# RFFE.net
KiCad netlist of a schematic drawn in Altium Designer
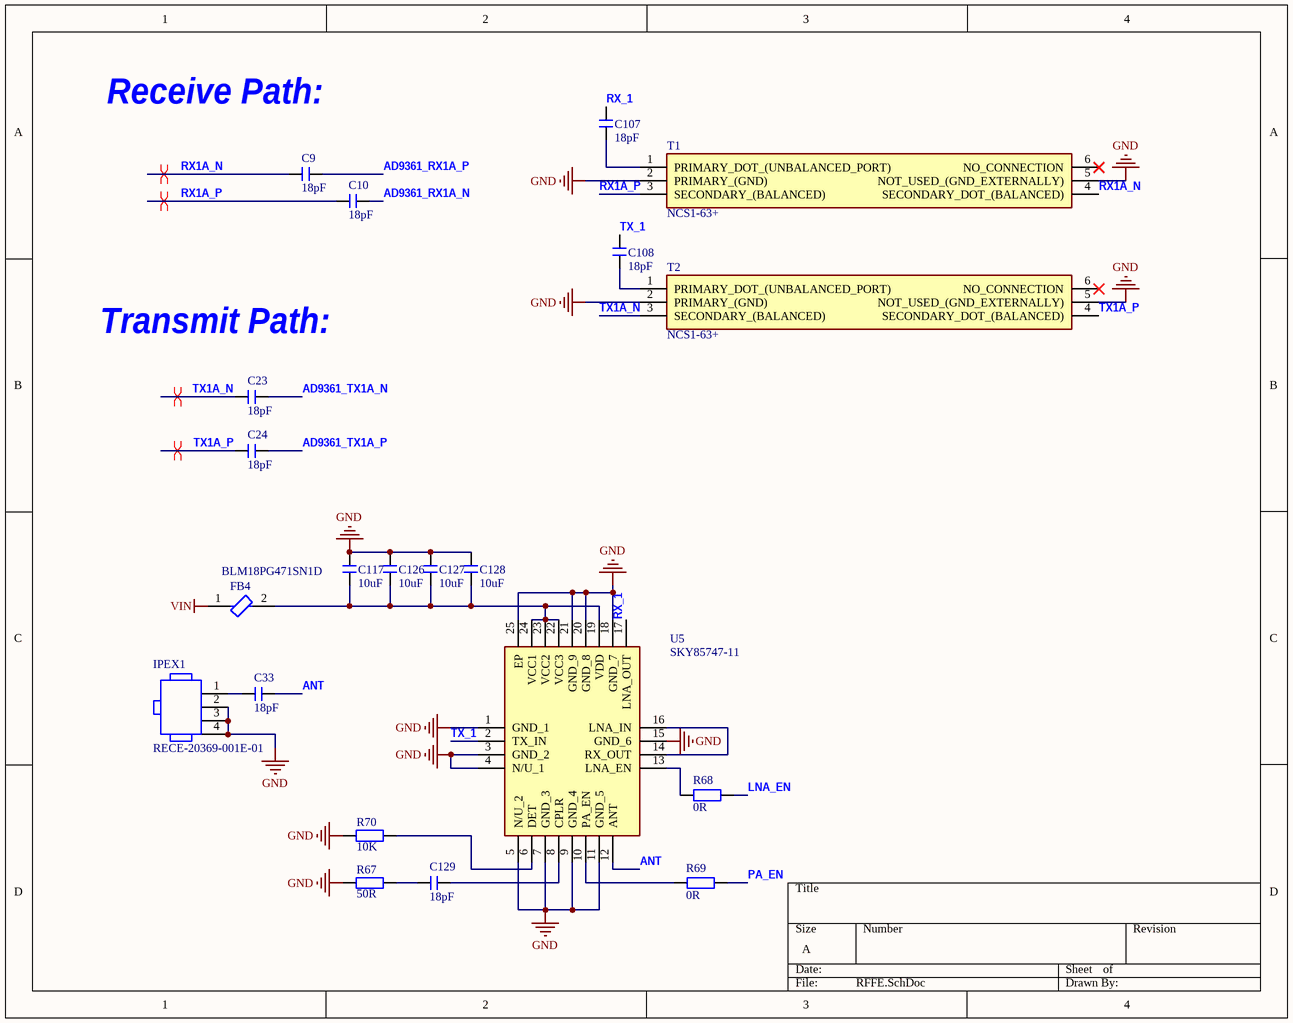
[diagram p0: RFFE.SchDoc]

(export (version "E")
  (design (tool "Eeschema 10.0.6"))
  (components
    (comp (ref "C9")
      (value "18pF")
      (footprint "SamacSys:CAP_0201")
      (description "无极性贴片电容")
      (fields (field (name "版权归属") "源创客"))
      (libsource (lib "源创客") (part "C"))
    )
    (comp (ref "C10")
      (value "18pF")
      (footprint "SamacSys:CAP_0201")
      (description "无极性贴片电容")
      (fields (field (name "版权归属") "源创客"))
      (libsource (lib "源创客") (part "C"))
    )
    (comp (ref "C23")
      (value "18pF")
      (footprint "SamacSys:CAP_0201")
      (description "无极性贴片电容")
      (fields (field (name "版权归属") "源创客"))
      (libsource (lib "源创客") (part "C"))
    )
    (comp (ref "C24")
      (value "18pF")
      (footprint "SamacSys:CAP_0201")
      (description "无极性贴片电容")
      (fields (field (name "版权归属") "源创客"))
      (libsource (lib "源创客") (part "C"))
    )
    (comp (ref "C33")
      (value "18pF")
      (footprint "SamacSys:CAP_0201")
      (description "无极性贴片电容")
      (fields (field (name "版权归属") "源创客"))
      (libsource (lib "源创客") (part "C"))
    )
    (comp (ref "C107")
      (value "18pF")
      (footprint "SamacSys:CAP_0201")
      (description "无极性贴片电容")
      (fields (field (name "版权归属") "源创客"))
      (libsource (lib "源创客") (part "C"))
    )
    (comp (ref "C108")
      (value "18pF")
      (footprint "SamacSys:CAP_0201")
      (description "无极性贴片电容")
      (fields (field (name "版权归属") "源创客"))
      (libsource (lib "源创客") (part "C"))
    )
    (comp (ref "C117")
      (value "10uF")
      (footprint "SamacSys:CAP_0402")
      (description "无极性贴片电容")
      (fields (field (name "版权归属") "源创客"))
      (libsource (lib "源创客") (part "C"))
    )
    (comp (ref "C126")
      (value "10uF")
      (footprint "SamacSys:CAP_0402")
      (description "无极性贴片电容")
      (fields (field (name "版权归属") "源创客"))
      (libsource (lib "源创客") (part "C"))
    )
    (comp (ref "C127")
      (value "10uF")
      (footprint "SamacSys:CAP_0402")
      (description "无极性贴片电容")
      (fields (field (name "版权归属") "源创客"))
      (libsource (lib "源创客") (part "C"))
    )
    (comp (ref "C128")
      (value "10uF")
      (footprint "SamacSys:CAP_0402")
      (description "无极性贴片电容")
      (fields (field (name "版权归属") "源创客"))
      (libsource (lib "源创客") (part "C"))
    )
    (comp (ref "C129")
      (value "18pF")
      (footprint "SamacSys:CAP_0201")
      (description "无极性贴片电容")
      (fields (field (name "版权归属") "源创客"))
      (libsource (lib "源创客") (part "C"))
    )
    (comp (ref "FB4")
      (value "BLM18PG471SN1D")
      (footprint "FP-BLM18-0_15-t0_8-MFG")
      (description "Chip Ferrite Bead, 0603, 470Ω @ 100MHz, 0.2Ω, 25%, 1A")
      (fields (field (name "TOLERANCE") "25%"))
      (libsource (lib "Altium Content Vault") (part "5f30dd21d616792df468990f7003faa"))
    )
    (comp (ref "IPEX1")
      (value "RECE-20369-001E-01")
      (footprint "TG-RECE-20369-001E-4_V")
      (description "RF Connector, Onboard Receptacle, IPEX MHFIII")
      (fields (field (name "MANUFACTURER") "Taoglas"))
      (libsource (lib "Altium Content Vault") (part "TG-RECE-20369-001E-01-4"))
    )
    (comp (ref "R67")
      (value "50R")
      (footprint "SamacSys:RES_0201")
      (description "Resistor")
      (libsource (lib "源创客") (part "Resistor"))
    )
    (comp (ref "R68")
      (value "0R")
      (footprint "SamacSys:RES_0402")
      (description "贴片电阻")
      (fields (field (name "版权归属") "源创客"))
      (libsource (lib "源创客") (part "R"))
    )
    (comp (ref "R69")
      (value "0R")
      (footprint "SamacSys:RES_0402")
      (description "贴片电阻")
      (fields (field (name "版权归属") "源创客"))
      (libsource (lib "源创客") (part "R"))
    )
    (comp (ref "R70")
      (value "10K")
      (footprint "SamacSys:RES_0201")
      (description "Resistor")
      (libsource (lib "源创客") (part "Resistor"))
    )
    (comp (ref "T1")
      (value "NCS1-63+")
      (footprint "SamacSys:NCS163")
      (description "Transformer")
      (fields (field (name "MOUSER PART NUMBER") "139-NCS1-63"))
      (libsource (lib "*") (part "NCS1-63+"))
    )
    (comp (ref "T2")
      (value "NCS1-63+")
      (footprint "SamacSys:NCS163")
      (description "Transformer")
      (fields (field (name "MOUSER PART NUMBER") "139-NCS1-63"))
      (libsource (lib "*") (part "NCS1-63+"))
    )
    (comp (ref "U5")
      (value "SKY85747-11")
      (footprint "SamacSys:SKY8574711")
      (description "Integrated Circuit")
      (libsource (lib "*") (part "SKY85747-11"))
    )
  )
  (nets
    (net (code "1") (name "/AD9361_RX1A_N") (class "Default")
      (node (ref "C10") (pin "2") (pinfunction "2_2") (pintype "passive"))
    )
    (net (code "2") (name "/AD9361_RX1A_P") (class "Default")
      (node (ref "C9") (pin "2") (pinfunction "2_2") (pintype "passive"))
    )
    (net (code "3") (name "/AD9361_TX1A_N") (class "Default")
      (node (ref "C23") (pin "2") (pinfunction "2_2") (pintype "passive"))
    )
    (net (code "4") (name "/AD9361_TX1A_P") (class "Default")
      (node (ref "C24") (pin "2") (pinfunction "2_2") (pintype "passive"))
    )
    (net (code "5") (name "/ANT") (class "Default")
      (node (ref "C33") (pin "2") (pinfunction "2_2") (pintype "passive"))
      (node (ref "U5") (pin "12") (pinfunction "ANT_12") (pintype "passive"))
    )
    (net (code "6") (name "/LNA_EN") (class "Default")
      (node (ref "R68") (pin "1") (pinfunction "1_1") (pintype "passive"))
    )
    (net (code "7") (name "/PA_EN") (class "Default")
      (node (ref "R69") (pin "1") (pinfunction "1_1") (pintype "passive"))
    )
    (net (code "8") (name "/RX1A_N") (class "Default")
      (node (ref "C9") (pin "1") (pinfunction "1_1") (pintype "passive"))
      (node (ref "T1") (pin "4") (pinfunction "SECONDARY_DOT_(BALANCED)_4") (pintype "passive"))
    )
    (net (code "9") (name "/RX1A_P") (class "Default")
      (node (ref "C10") (pin "1") (pinfunction "1_1") (pintype "passive"))
      (node (ref "T1") (pin "3") (pinfunction "SECONDARY_(BALANCED)_3") (pintype "passive"))
    )
    (net (code "10") (name "/RX_1") (class "Default")
      (node (ref "C107") (pin "2") (pinfunction "2_2") (pintype "passive"))
      (node (ref "U5") (pin "17") (pinfunction "LNA_OUT_17") (pintype "passive"))
    )
    (net (code "11") (name "/TX1A_N") (class "Default")
      (node (ref "C23") (pin "1") (pinfunction "1_1") (pintype "passive"))
      (node (ref "T2") (pin "3") (pinfunction "SECONDARY_(BALANCED)_3") (pintype "passive"))
    )
    (net (code "12") (name "/TX1A_P") (class "Default")
      (node (ref "C24") (pin "1") (pinfunction "1_1") (pintype "passive"))
      (node (ref "T2") (pin "4") (pinfunction "SECONDARY_DOT_(BALANCED)_4") (pintype "passive"))
    )
    (net (code "13") (name "/TX_1") (class "Default")
      (node (ref "C108") (pin "2") (pinfunction "2_2") (pintype "passive"))
      (node (ref "U5") (pin "2") (pinfunction "TX_IN_2") (pintype "passive"))
    )
    (net (code "14") (name "GND") (class "Default")
      (node (ref "C117") (pin "2") (pinfunction "2_2") (pintype "passive"))
      (node (ref "C126") (pin "2") (pinfunction "2_2") (pintype "passive"))
      (node (ref "C127") (pin "2") (pinfunction "2_2") (pintype "passive"))
      (node (ref "C128") (pin "2") (pinfunction "2_2") (pintype "passive"))
      (node (ref "IPEX1") (pin "2") (pinfunction "2_2") (pintype "passive"))
      (node (ref "IPEX1") (pin "3") (pinfunction "3_3") (pintype "passive"))
      (node (ref "IPEX1") (pin "4") (pinfunction "4_4") (pintype "passive"))
      (node (ref "R67") (pin "2") (pinfunction "2_2") (pintype "passive"))
      (node (ref "R70") (pin "2") (pinfunction "2_2") (pintype "passive"))
      (node (ref "T1") (pin "2") (pinfunction "PRIMARY_(GND)_2") (pintype "passive"))
      (node (ref "T1") (pin "5") (pinfunction "NOT_USED_(GND_EXTERNALLY)_5") (pintype "passive"))
      (node (ref "T2") (pin "2") (pinfunction "PRIMARY_(GND)_2") (pintype "passive"))
      (node (ref "T2") (pin "5") (pinfunction "NOT_USED_(GND_EXTERNALLY)_5") (pintype "passive"))
      (node (ref "U5") (pin "1") (pinfunction "GND_1_1") (pintype "passive"))
      (node (ref "U5") (pin "11") (pinfunction "GND_5_11") (pintype "passive"))
      (node (ref "U5") (pin "15") (pinfunction "GND_6_15") (pintype "passive"))
      (node (ref "U5") (pin "18") (pinfunction "GND_7_18") (pintype "passive"))
      (node (ref "U5") (pin "20") (pinfunction "GND_8_20") (pintype "passive"))
      (node (ref "U5") (pin "21") (pinfunction "GND_9_21") (pintype "passive"))
      (node (ref "U5") (pin "25") (pinfunction "EP_25") (pintype "passive"))
      (node (ref "U5") (pin "3") (pinfunction "GND_2_3") (pintype "passive"))
      (node (ref "U5") (pin "4") (pinfunction "N/U_1_4") (pintype "passive"))
      (node (ref "U5") (pin "5") (pinfunction "N/U_2_5") (pintype "passive"))
      (node (ref "U5") (pin "7") (pinfunction "GND_3_7") (pintype "passive"))
      (node (ref "U5") (pin "9") (pinfunction "GND_4_9") (pintype "passive"))
    )
    (net (code "15") (name "Net-(C33-Pad1)") (class "Default")
      (node (ref "C33") (pin "1") (pinfunction "1_1") (pintype "passive"))
      (node (ref "IPEX1") (pin "1") (pinfunction "1_1") (pintype "passive"))
    )
    (net (code "16") (name "Net-(C129-Pad1)") (class "Default")
      (node (ref "C129") (pin "1") (pinfunction "1_1") (pintype "passive"))
      (node (ref "R67") (pin "1") (pinfunction "1_1") (pintype "passive"))
    )
    (net (code "17") (name "Net-(T1-PRIMARY_DOT_(UNBALANCED_PORT))") (class "Default")
      (node (ref "C107") (pin "1") (pinfunction "1_1") (pintype "passive"))
      (node (ref "T1") (pin "1") (pinfunction "PRIMARY_DOT_(UNBALANCED_PORT)_1") (pintype "passive"))
    )
    (net (code "18") (name "Net-(T2-PRIMARY_DOT_(UNBALANCED_PORT))") (class "Default")
      (node (ref "C108") (pin "1") (pinfunction "1_1") (pintype "passive"))
      (node (ref "T2") (pin "1") (pinfunction "PRIMARY_DOT_(UNBALANCED_PORT)_1") (pintype "passive"))
    )
    (net (code "19") (name "Net-(U5-CPLR)") (class "Default")
      (node (ref "C129") (pin "2") (pinfunction "2_2") (pintype "passive"))
      (node (ref "U5") (pin "8") (pinfunction "CPLR_8") (pintype "passive"))
    )
    (net (code "20") (name "Net-(U5-DET)") (class "Default")
      (node (ref "R70") (pin "1") (pinfunction "1_1") (pintype "passive"))
      (node (ref "U5") (pin "6") (pinfunction "DET_6") (pintype "passive"))
    )
    (net (code "21") (name "Net-(U5-LNA_EN)") (class "Default")
      (node (ref "R68") (pin "2") (pinfunction "2_2") (pintype "passive"))
      (node (ref "U5") (pin "13") (pinfunction "LNA_EN_13") (pintype "passive"))
    )
    (net (code "22") (name "Net-(U5-LNA_IN)") (class "Default")
      (node (ref "U5") (pin "14") (pinfunction "RX_OUT_14") (pintype "passive"))
      (node (ref "U5") (pin "16") (pinfunction "LNA_IN_16") (pintype "passive"))
    )
    (net (code "23") (name "Net-(U5-PA_EN)") (class "Default")
      (node (ref "R69") (pin "2") (pinfunction "2_2") (pintype "passive"))
      (node (ref "U5") (pin "10") (pinfunction "PA_EN_10") (pintype "passive"))
    )
    (net (code "24") (name "Net-(U5-VCC1)") (class "Default")
      (node (ref "C117") (pin "1") (pinfunction "1_1") (pintype "passive"))
      (node (ref "C126") (pin "1") (pinfunction "1_1") (pintype "passive"))
      (node (ref "C127") (pin "1") (pinfunction "1_1") (pintype "passive"))
      (node (ref "C128") (pin "1") (pinfunction "1_1") (pintype "passive"))
      (node (ref "FB4") (pin "2") (pinfunction "2_2") (pintype "passive"))
      (node (ref "U5") (pin "19") (pinfunction "VDD_19") (pintype "passive"))
      (node (ref "U5") (pin "22") (pinfunction "VCC3_22") (pintype "passive"))
      (node (ref "U5") (pin "23") (pinfunction "VCC2_23") (pintype "passive"))
      (node (ref "U5") (pin "24") (pinfunction "VCC1_24") (pintype "passive"))
    )
    (net (code "25") (name "VIN") (class "Default")
      (node (ref "FB4") (pin "1") (pinfunction "1_1") (pintype "passive"))
    )
    (net (code "26") (name "unconnected-(T1-NO_CONNECTION-Pad6)") (class "Default")
      (node (ref "T1") (pin "6") (pinfunction "NO_CONNECTION_6") (pintype "passive+no_connect"))
    )
    (net (code "27") (name "unconnected-(T2-NO_CONNECTION-Pad6)") (class "Default")
      (node (ref "T2") (pin "6") (pinfunction "NO_CONNECTION_6") (pintype "passive+no_connect"))
    )
  )
)
